# parallel_R_LED_buttons.net
KiCad netlist of a schematic drawn in EAGLE
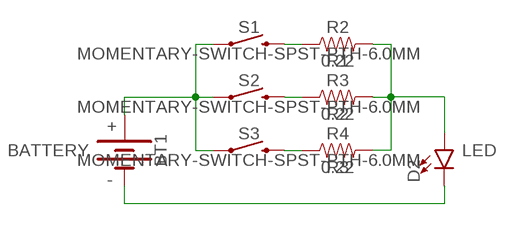
[diagram p0: schematic, sheet 1]

(export (version "E")
  (design (tool "Eeschema 10.0.6"))
  (components
    (comp (ref "BT1")
      (value "BATTERY-9V")
      (footprint "eagle-import:BATTCON_9V")
      (libsource (lib "eagle-import") (part "BATTERY-9V"))
    )
    (comp (ref "D2")
      (value "LED5MM")
      (footprint "eagle-import:LED_5MM")
      (libsource (lib "eagle-import") (part "LED5MM"))
    )
    (comp (ref "R2")
      (value "0.22")
      (footprint "eagle-import:0805")
      (libsource (lib "eagle-import") (part "0.22OHM-0805-1/4W-1%"))
    )
    (comp (ref "R3")
      (value "0.22")
      (footprint "eagle-import:0805")
      (libsource (lib "eagle-import") (part "0.22OHM-0805-1/4W-1%"))
    )
    (comp (ref "R4")
      (value "0.22")
      (footprint "eagle-import:0805")
      (libsource (lib "eagle-import") (part "0.22OHM-0805-1/4W-1%"))
    )
    (comp (ref "S1")
      (value "MOMENTARY-SWITCH-SPST-PTH-6.0MM")
      (footprint "eagle-import:TACTILE_SWITCH_PTH_6.0MM")
      (libsource (lib "eagle-import") (part "MOMENTARY-SWITCH-SPST-PTH-6.0MM"))
    )
    (comp (ref "S2")
      (value "MOMENTARY-SWITCH-SPST-PTH-6.0MM")
      (footprint "eagle-import:TACTILE_SWITCH_PTH_6.0MM")
      (libsource (lib "eagle-import") (part "MOMENTARY-SWITCH-SPST-PTH-6.0MM"))
    )
    (comp (ref "S3")
      (value "MOMENTARY-SWITCH-SPST-PTH-6.0MM")
      (footprint "eagle-import:TACTILE_SWITCH_PTH_6.0MM")
      (libsource (lib "eagle-import") (part "MOMENTARY-SWITCH-SPST-PTH-6.0MM"))
    )
  )
  (nets
    (net (code "1") (name "Net-(BT1-Pad+)") (class "Default")
      (node (ref "BT1") (pin "+") (pinfunction "+_+") (pintype "power_in"))
      (node (ref "S1") (pin "1") (pinfunction "1_1") (pintype "passive"))
      (node (ref "S2") (pin "1") (pinfunction "1_1") (pintype "passive"))
      (node (ref "S3") (pin "1") (pinfunction "1_1") (pintype "passive"))
    )
    (net (code "2") (name "Net-(D2-C)") (class "Default")
      (node (ref "BT1") (pin "-") (pinfunction "-_-") (pintype "power_in"))
      (node (ref "D2") (pin "K") (pinfunction "C_K") (pintype "passive"))
    )
    (net (code "3") (name "Net-(D2-PadA)") (class "Default")
      (node (ref "D2") (pin "A") (pinfunction "A_A") (pintype "passive"))
      (node (ref "R2") (pin "2") (pinfunction "2_2") (pintype "passive"))
      (node (ref "R3") (pin "2") (pinfunction "2_2") (pintype "passive"))
      (node (ref "R4") (pin "2") (pinfunction "2_2") (pintype "passive"))
    )
    (net (code "4") (name "Net-(S1-2)") (class "Default")
      (node (ref "R2") (pin "1") (pinfunction "1_1") (pintype "passive"))
      (node (ref "S1") (pin "3") (pinfunction "2_3") (pintype "passive"))
    )
    (net (code "5") (name "Net-(S2-2)") (class "Default")
      (node (ref "R3") (pin "1") (pinfunction "1_1") (pintype "passive"))
      (node (ref "S2") (pin "3") (pinfunction "2_3") (pintype "passive"))
    )
    (net (code "6") (name "Net-(S3-2)") (class "Default")
      (node (ref "R4") (pin "1") (pinfunction "1_1") (pintype "passive"))
      (node (ref "S3") (pin "3") (pinfunction "2_3") (pintype "passive"))
    )
  )
)
